# buttons.net
KiCad netlist of a schematic drawn in Altium Designer
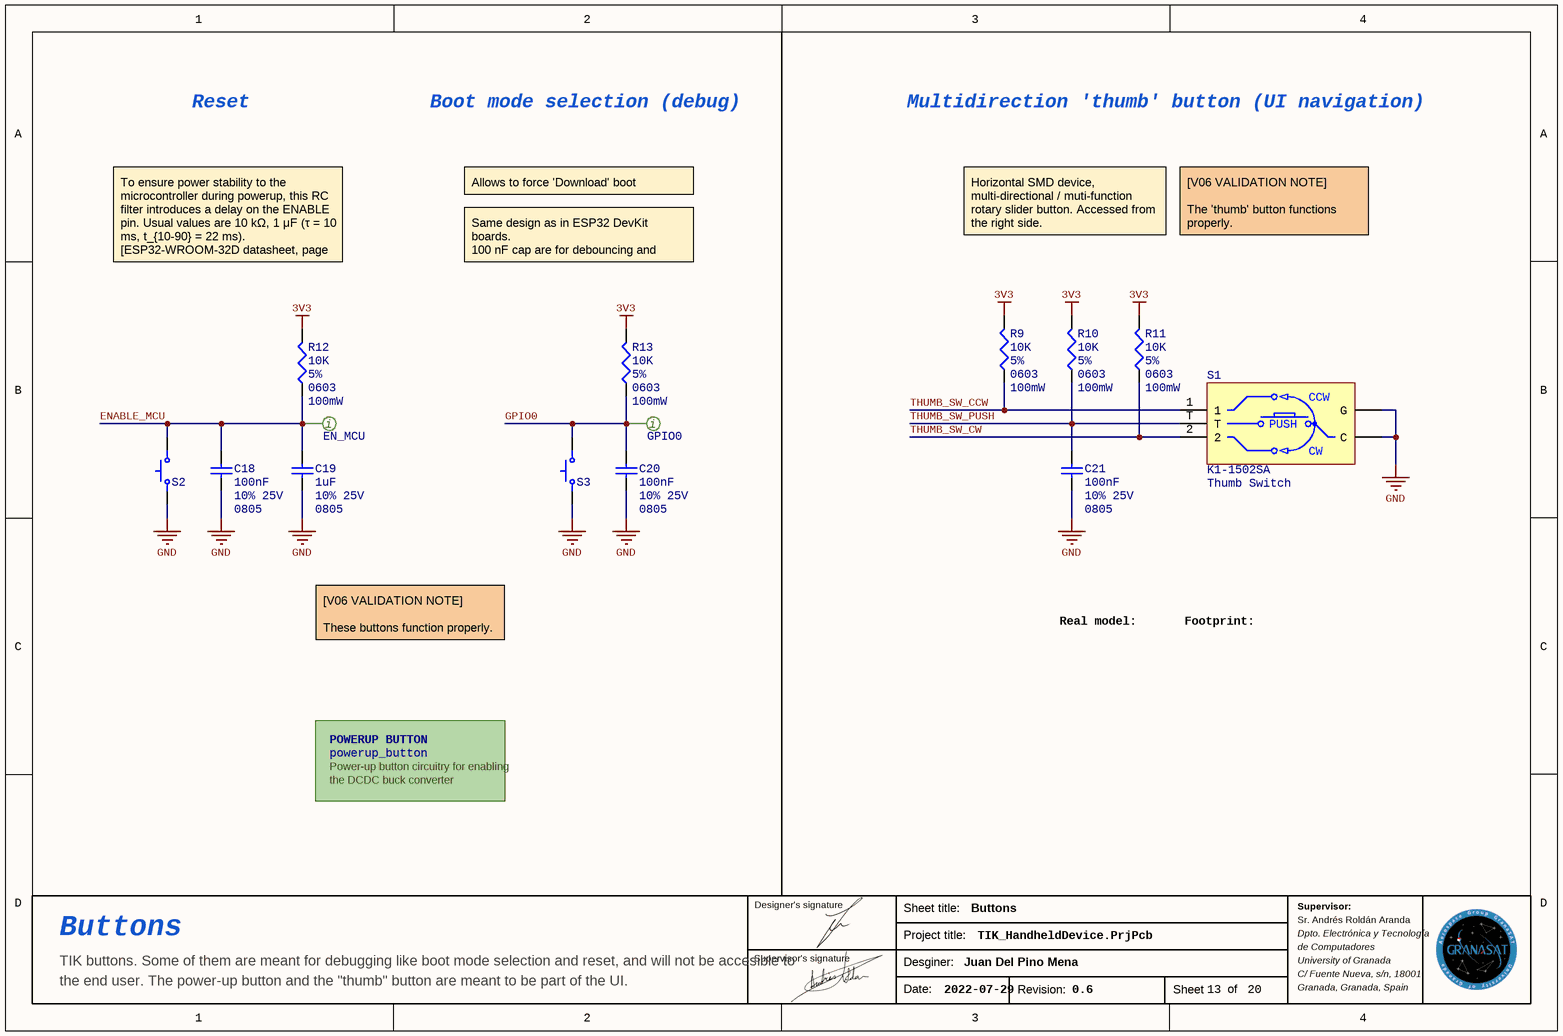
[diagram p0: buttons.SchDoc]

(export (version "E")
  (design (tool "Eeschema 10.0.6"))
  (components
    (comp (ref "C18")
      (value "100nF")
      (footprint "CAP 0805_2012")
      (description "Ceramic cap size 0805")
      (fields
        (field (name "TOLERANCE") "10% 25V")
        (field (name "PACKAGEDESCRIPTION") "0805")
        (field (name "Comment") "Cap_cer_0805")
      )
      (libsource (lib "tik_handheld_schlib") (part "Cap_cer_0805_100nF_10%"))
    )
    (comp (ref "C19")
      (value "1uF")
      (footprint "CAP 0805_2012")
      (description "Ceramic cap size 0805")
      (fields
        (field (name "TOLERANCE") "10% 25V")
        (field (name "PACKAGEDESCRIPTION") "0805")
        (field (name "Comment") "Cap_cer_0805")
      )
      (libsource (lib "tik_handheld_schlib") (part "Cap_cer_0805_1uF_10%"))
    )
    (comp (ref "C20")
      (value "100nF")
      (footprint "CAP 0805_2012")
      (description "Ceramic cap size 0805")
      (fields
        (field (name "TOLERANCE") "10% 25V")
        (field (name "PACKAGEDESCRIPTION") "0805")
        (field (name "Comment") "Cap_cer_0805")
      )
      (libsource (lib "tik_handheld_schlib") (part "Cap_cer_0805_100nF_10%"))
    )
    (comp (ref "C21")
      (value "100nF")
      (footprint "CAP 0805_2012")
      (description "Ceramic cap size 0805")
      (fields
        (field (name "TOLERANCE") "10% 25V")
        (field (name "PACKAGEDESCRIPTION") "0805")
        (field (name "Comment") "Cap_cer_0805")
      )
      (libsource (lib "tik_handheld_schlib") (part "Cap_cer_0805_100nF_10%"))
    )
    (comp (ref "EN_MCU")
      (value "Test Point Pad dual sided")
      (footprint "TEST POINT PAD")
      (description "Test point - PCB Pad dual sided")
      (libsource (lib "tik_handheld_schlib") (part "Test Point Pad dual sided"))
    )
    (comp (ref "GPIO0")
      (value "Test Point Pad dual sided")
      (footprint "TEST POINT PAD")
      (description "Test point - PCB Pad dual sided")
      (libsource (lib "tik_handheld_schlib") (part "Test Point Pad dual sided"))
    )
    (comp (ref "R9")
      (value "10K")
      (footprint "RES 0603_1608")
      (description "Res size 0603 SMD mounting, low power")
      (fields
        (field (name "TOLERANCE") "5%")
        (field (name "PACKAGEDESCRIPTION") "0603")
        (field (name "POWERDISIPATED") "100mW")
        (field (name "Comment") "Res_0603_10K_5%_100mW_1")
      )
      (libsource (lib "tik_handheld_schlib") (part "Res_0603_10K_5%_100mW_1"))
    )
    (comp (ref "R10")
      (value "10K")
      (footprint "RES 0603_1608")
      (description "Res size 0603 SMD mounting, low power")
      (fields
        (field (name "TOLERANCE") "5%")
        (field (name "PACKAGEDESCRIPTION") "0603")
        (field (name "POWERDISIPATED") "100mW")
        (field (name "Comment") "Res_0603_10K_5%_100mW_1")
      )
      (libsource (lib "tik_handheld_schlib") (part "Res_0603_10K_5%_100mW_1"))
    )
    (comp (ref "R11")
      (value "10K")
      (footprint "RES 0603_1608")
      (description "Res size 0603 SMD mounting, low power")
      (fields
        (field (name "TOLERANCE") "5%")
        (field (name "PACKAGEDESCRIPTION") "0603")
        (field (name "POWERDISIPATED") "100mW")
        (field (name "Comment") "Res_0603_10K_5%_100mW_1")
      )
      (libsource (lib "tik_handheld_schlib") (part "Res_0603_10K_5%_100mW_1"))
    )
    (comp (ref "R12")
      (value "10K")
      (footprint "RES 0603_1608")
      (description "Res size 0603 SMD mounting, low power")
      (fields
        (field (name "TOLERANCE") "5%")
        (field (name "PACKAGEDESCRIPTION") "0603")
        (field (name "POWERDISIPATED") "100mW")
        (field (name "Comment") "Res_0603_10K_5%_100mW_1")
      )
      (libsource (lib "tik_handheld_schlib") (part "Res_0603_10K_5%_100mW_1"))
    )
    (comp (ref "R13")
      (value "10K")
      (footprint "RES 0603_1608")
      (description "Res size 0603 SMD mounting, low power")
      (fields
        (field (name "TOLERANCE") "5%")
        (field (name "PACKAGEDESCRIPTION") "0603")
        (field (name "POWERDISIPATED") "100mW")
        (field (name "Comment") "Res_0603_10K_5%_100mW_1")
      )
      (libsource (lib "tik_handheld_schlib") (part "Res_0603_10K_5%_100mW_1"))
    )
    (comp (ref "S1")
      (value "SWITCH Multidirection Slide Push Button SMD TS-003")
      (footprint "SWITCH THUMB MULTIDIRECTION K1-1502SA-01")
      (fields (field (name "PART") "K1-1502SA") (field (name "TYPE") "Thumb Switch"))
      (libsource (lib "tik_handheld_schlib") (part "SWITCH Multidirection Slide Push Button SMD TS-003"))
    )
    (comp (ref "S2")
      (value "Button")
      (footprint "button generic")
      (description "Generic 2 pin button")
      (libsource (lib "tik_handheld_schlib") (part "Button"))
    )
    (comp (ref "S3")
      (value "Button")
      (footprint "button generic")
      (description "Generic 2 pin button")
      (libsource (lib "tik_handheld_schlib") (part "Button"))
    )
  )
  (nets
    (net (code "1") (name "/ENABLE_MCU") (class "Default")
      (node (ref "C18") (pin "2") (pinfunction "2_2") (pintype "passive"))
      (node (ref "C19") (pin "2") (pinfunction "2_2") (pintype "passive"))
      (node (ref "EN_MCU") (pin "1") (pinfunction "1_1") (pintype "passive"))
      (node (ref "R12") (pin "1") (pinfunction "1_1") (pintype "passive"))
      (node (ref "S2") (pin "2") (pinfunction "2_2") (pintype "passive"))
    )
    (net (code "2") (name "/GPIO0") (class "Default")
      (node (ref "C20") (pin "2") (pinfunction "2_2") (pintype "passive"))
      (node (ref "GPIO0") (pin "1") (pinfunction "1_1") (pintype "passive"))
      (node (ref "R13") (pin "1") (pinfunction "1_1") (pintype "passive"))
      (node (ref "S3") (pin "2") (pinfunction "2_2") (pintype "passive"))
    )
    (net (code "3") (name "/THUMB_SW_CCW") (class "Default")
      (node (ref "R9") (pin "1") (pinfunction "1_1") (pintype "passive"))
      (node (ref "S1") (pin "1") (pinfunction "1_1") (pintype "passive"))
    )
    (net (code "4") (name "/THUMB_SW_CW") (class "Default")
      (node (ref "R11") (pin "1") (pinfunction "1_1") (pintype "passive"))
      (node (ref "S1") (pin "2") (pinfunction "2_2") (pintype "passive"))
    )
    (net (code "5") (name "/THUMB_SW_PUSH") (class "Default")
      (node (ref "C21") (pin "2") (pinfunction "2_2") (pintype "passive"))
      (node (ref "R10") (pin "1") (pinfunction "1_1") (pintype "passive"))
      (node (ref "S1") (pin "T") (pinfunction "T_T") (pintype "passive"))
    )
    (net (code "6") (name "3V3") (class "Default")
      (node (ref "R10") (pin "2") (pinfunction "2_2") (pintype "passive"))
      (node (ref "R11") (pin "2") (pinfunction "2_2") (pintype "passive"))
      (node (ref "R12") (pin "2") (pinfunction "2_2") (pintype "passive"))
      (node (ref "R13") (pin "2") (pinfunction "2_2") (pintype "passive"))
      (node (ref "R9") (pin "2") (pinfunction "2_2") (pintype "passive"))
    )
    (net (code "7") (name "GND") (class "Default")
      (node (ref "C18") (pin "1") (pinfunction "1_1") (pintype "passive"))
      (node (ref "C19") (pin "1") (pinfunction "1_1") (pintype "passive"))
      (node (ref "C20") (pin "1") (pinfunction "1_1") (pintype "passive"))
      (node (ref "C21") (pin "1") (pinfunction "1_1") (pintype "passive"))
      (node (ref "S1") (pin "C") (pinfunction "C_C") (pintype "passive"))
      (node (ref "S1") (pin "G") (pinfunction "G_G") (pintype "passive"))
      (node (ref "S2") (pin "1") (pinfunction "1_1") (pintype "passive"))
      (node (ref "S3") (pin "1") (pinfunction "1_1") (pintype "passive"))
    )
  )
)
